# IN14_board.net
KiCad netlist of a schematic drawn in EAGLE
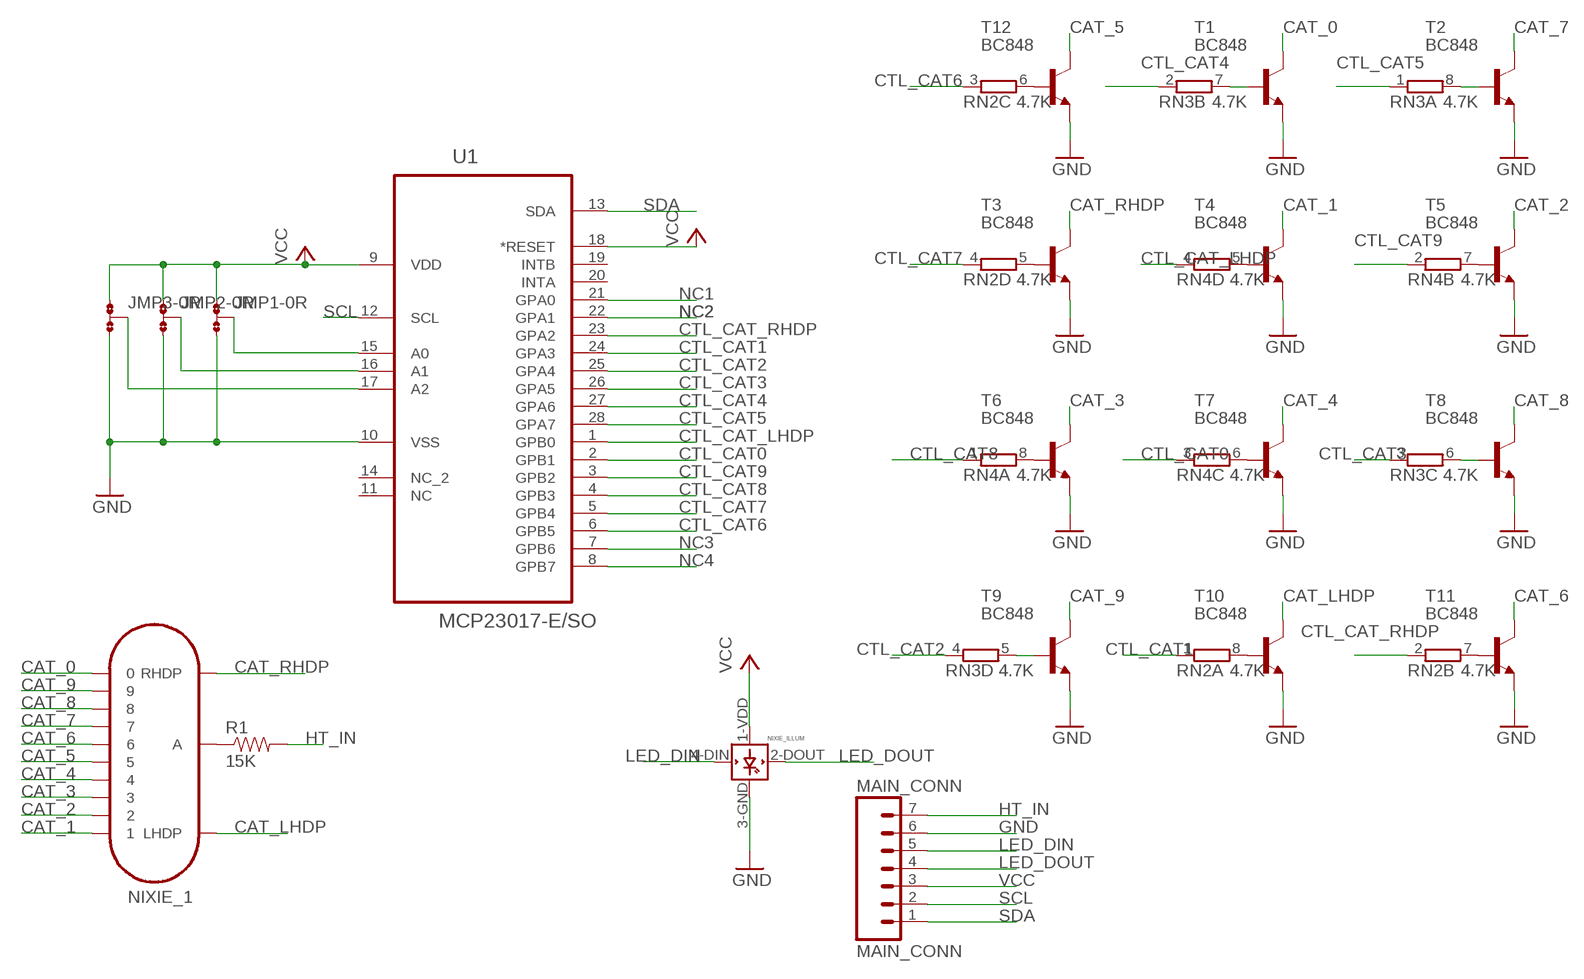
[diagram p0: schematic, sheet 1]

(export (version "E")
  (design (tool "Eeschema 10.0.6"))
  (components
    (comp (ref "JMP1")
      (value "0R-JUMPA")
      (footprint "eagle-import:A0R-JMP")
      (libsource (lib "eagle-import") (part "0R-JUMPA"))
    )
    (comp (ref "JMP2")
      (value "0R-JUMPA")
      (footprint "eagle-import:A0R-JMP")
      (libsource (lib "eagle-import") (part "0R-JUMPA"))
    )
    (comp (ref "JMP3")
      (value "0R-JUMPA")
      (footprint "eagle-import:A0R-JMP")
      (libsource (lib "eagle-import") (part "0R-JUMPA"))
    )
    (comp (ref "MAIN_CONN")
      (value "MAIN_CONN")
      (footprint "eagle-import:1X07_LONGPADS")
      (libsource (lib "eagle-import") (part "M07LONGPADS"))
    )
    (comp (ref "NIXIE_1")
      (value "IN-14")
      (footprint "eagle-import:IN-14")
      (libsource (lib "eagle-import") (part "IN-14"))
    )
    (comp (ref "NIXIE_ILLUM")
      (value "WS2812B")
      (footprint "eagle-import:WS2812B")
      (libsource (lib "eagle-import") (part "WS2812B"))
    )
    (comp (ref "R1")
      (value "15K")
      (footprint "eagle-import:0603-RES")
      (libsource (lib "eagle-import") (part "15KOHM1/10W1%(0603)0603"))
    )
    (comp (ref "RN2")
      (value "4.7K")
      (footprint "eagle-import:EXB38V")
      (libsource (lib "eagle-import") (part "4R-NEXB38V"))
    )
    (comp (ref "RN3")
      (value "4.7K")
      (footprint "eagle-import:EXB38V")
      (libsource (lib "eagle-import") (part "4R-NEXB38V"))
    )
    (comp (ref "RN4")
      (value "4.7K")
      (footprint "eagle-import:EXB38V")
      (libsource (lib "eagle-import") (part "4R-NEXB38V"))
    )
    (comp (ref "T1")
      (value "BC848")
      (footprint "eagle-import:SOT23")
      (libsource (lib "eagle-import") (part "BC848"))
    )
    (comp (ref "T2")
      (value "BC848")
      (footprint "eagle-import:SOT23")
      (libsource (lib "eagle-import") (part "BC848"))
    )
    (comp (ref "T3")
      (value "BC848")
      (footprint "eagle-import:SOT23")
      (libsource (lib "eagle-import") (part "BC848"))
    )
    (comp (ref "T4")
      (value "BC848")
      (footprint "eagle-import:SOT23")
      (libsource (lib "eagle-import") (part "BC848"))
    )
    (comp (ref "T5")
      (value "BC848")
      (footprint "eagle-import:SOT23")
      (libsource (lib "eagle-import") (part "BC848"))
    )
    (comp (ref "T6")
      (value "BC848")
      (footprint "eagle-import:SOT23")
      (libsource (lib "eagle-import") (part "BC848"))
    )
    (comp (ref "T7")
      (value "BC848")
      (footprint "eagle-import:SOT23")
      (libsource (lib "eagle-import") (part "BC848"))
    )
    (comp (ref "T8")
      (value "BC848")
      (footprint "eagle-import:SOT23")
      (libsource (lib "eagle-import") (part "BC848"))
    )
    (comp (ref "T9")
      (value "BC848")
      (footprint "eagle-import:SOT23")
      (libsource (lib "eagle-import") (part "BC848"))
    )
    (comp (ref "T10")
      (value "BC848")
      (footprint "eagle-import:SOT23")
      (libsource (lib "eagle-import") (part "BC848"))
    )
    (comp (ref "T11")
      (value "BC848")
      (footprint "eagle-import:SOT23")
      (libsource (lib "eagle-import") (part "BC848"))
    )
    (comp (ref "T12")
      (value "BC848")
      (footprint "eagle-import:SOT23")
      (libsource (lib "eagle-import") (part "BC848"))
    )
    (comp (ref "U1")
      (value "MCP23017-E/SO")
      (footprint "eagle-import:SOIC127P1032X265-28N")
      (libsource (lib "eagle-import") (part "MCP23017-E/SO"))
    )
  )
  (nets
    (net (code "1") (name "/CAT_0") (class "Default")
      (node (ref "NIXIE_1") (pin "0") (pinfunction "0_0") (pintype "bidirectional"))
      (node (ref "T1") (pin "3") (pinfunction "C_3") (pintype "passive"))
    )
    (net (code "2") (name "/CAT_1") (class "Default")
      (node (ref "NIXIE_1") (pin "1") (pinfunction "1_1") (pintype "bidirectional"))
      (node (ref "T4") (pin "3") (pinfunction "C_3") (pintype "passive"))
    )
    (net (code "3") (name "/CAT_2") (class "Default")
      (node (ref "NIXIE_1") (pin "2") (pinfunction "2_2") (pintype "bidirectional"))
      (node (ref "T5") (pin "3") (pinfunction "C_3") (pintype "passive"))
    )
    (net (code "4") (name "/CAT_3") (class "Default")
      (node (ref "NIXIE_1") (pin "3") (pinfunction "3_3") (pintype "bidirectional"))
      (node (ref "T6") (pin "3") (pinfunction "C_3") (pintype "passive"))
    )
    (net (code "5") (name "/CAT_4") (class "Default")
      (node (ref "NIXIE_1") (pin "4") (pinfunction "4_4") (pintype "bidirectional"))
      (node (ref "T7") (pin "3") (pinfunction "C_3") (pintype "passive"))
    )
    (net (code "6") (name "/CAT_5") (class "Default")
      (node (ref "NIXIE_1") (pin "5") (pinfunction "5_5") (pintype "bidirectional"))
      (node (ref "T12") (pin "3") (pinfunction "C_3") (pintype "passive"))
    )
    (net (code "7") (name "/CAT_6") (class "Default")
      (node (ref "NIXIE_1") (pin "6") (pinfunction "6_6") (pintype "bidirectional"))
      (node (ref "T11") (pin "3") (pinfunction "C_3") (pintype "passive"))
    )
    (net (code "8") (name "/CAT_7") (class "Default")
      (node (ref "NIXIE_1") (pin "7") (pinfunction "7_7") (pintype "bidirectional"))
      (node (ref "T2") (pin "3") (pinfunction "C_3") (pintype "passive"))
    )
    (net (code "9") (name "/CAT_8") (class "Default")
      (node (ref "NIXIE_1") (pin "8") (pinfunction "8_8") (pintype "bidirectional"))
      (node (ref "T8") (pin "3") (pinfunction "C_3") (pintype "passive"))
    )
    (net (code "10") (name "/CAT_9") (class "Default")
      (node (ref "NIXIE_1") (pin "9") (pinfunction "9_9") (pintype "bidirectional"))
      (node (ref "T9") (pin "3") (pinfunction "C_3") (pintype "passive"))
    )
    (net (code "11") (name "/CAT_LHDP") (class "Default")
      (node (ref "NIXIE_1") (pin "LHDP") (pinfunction "LHDP_LHDP") (pintype "bidirectional"))
      (node (ref "T10") (pin "3") (pinfunction "C_3") (pintype "passive"))
    )
    (net (code "12") (name "/CAT_RHDP") (class "Default")
      (node (ref "NIXIE_1") (pin "RHDP") (pinfunction "RHDP_RHDP") (pintype "bidirectional"))
      (node (ref "T3") (pin "3") (pinfunction "C_3") (pintype "passive"))
    )
    (net (code "13") (name "/CTL_CAT0") (class "Default")
      (node (ref "RN4") (pin "3") (pinfunction "1_3") (pintype "passive"))
      (node (ref "U1") (pin "2") (pinfunction "GPB1_2") (pintype "bidirectional"))
    )
    (net (code "14") (name "/CTL_CAT1") (class "Default")
      (node (ref "RN2") (pin "1") (pinfunction "1_1") (pintype "passive"))
      (node (ref "U1") (pin "24") (pinfunction "GPA3_24") (pintype "bidirectional"))
    )
    (net (code "15") (name "/CTL_CAT2") (class "Default")
      (node (ref "RN3") (pin "4") (pinfunction "1_4") (pintype "passive"))
      (node (ref "U1") (pin "25") (pinfunction "GPA4_25") (pintype "bidirectional"))
    )
    (net (code "16") (name "/CTL_CAT3") (class "Default")
      (node (ref "RN3") (pin "3") (pinfunction "1_3") (pintype "passive"))
      (node (ref "U1") (pin "26") (pinfunction "GPA5_26") (pintype "bidirectional"))
    )
    (net (code "17") (name "/CTL_CAT4") (class "Default")
      (node (ref "RN3") (pin "2") (pinfunction "1_2") (pintype "passive"))
      (node (ref "U1") (pin "27") (pinfunction "GPA6_27") (pintype "bidirectional"))
    )
    (net (code "18") (name "/CTL_CAT5") (class "Default")
      (node (ref "RN3") (pin "1") (pinfunction "1_1") (pintype "passive"))
      (node (ref "U1") (pin "28") (pinfunction "GPA7_28") (pintype "bidirectional"))
    )
    (net (code "19") (name "/CTL_CAT6") (class "Default")
      (node (ref "RN2") (pin "3") (pinfunction "1_3") (pintype "passive"))
      (node (ref "U1") (pin "6") (pinfunction "GPB5_6") (pintype "bidirectional"))
    )
    (net (code "20") (name "/CTL_CAT7") (class "Default")
      (node (ref "RN2") (pin "4") (pinfunction "1_4") (pintype "passive"))
      (node (ref "U1") (pin "5") (pinfunction "GPB4_5") (pintype "bidirectional"))
    )
    (net (code "21") (name "/CTL_CAT8") (class "Default")
      (node (ref "RN4") (pin "1") (pinfunction "1_1") (pintype "passive"))
      (node (ref "U1") (pin "4") (pinfunction "GPB3_4") (pintype "bidirectional"))
    )
    (net (code "22") (name "/CTL_CAT9") (class "Default")
      (node (ref "RN4") (pin "2") (pinfunction "1_2") (pintype "passive"))
      (node (ref "U1") (pin "3") (pinfunction "GPB2_3") (pintype "bidirectional"))
    )
    (net (code "23") (name "/CTL_CAT_LHDP") (class "Default")
      (node (ref "RN4") (pin "4") (pinfunction "1_4") (pintype "passive"))
      (node (ref "U1") (pin "1") (pinfunction "GPB0_1") (pintype "bidirectional"))
    )
    (net (code "24") (name "/CTL_CAT_RHDP") (class "Default")
      (node (ref "RN2") (pin "2") (pinfunction "1_2") (pintype "passive"))
      (node (ref "U1") (pin "23") (pinfunction "GPA2_23") (pintype "bidirectional"))
    )
    (net (code "25") (name "/HT_IN") (class "Default")
      (node (ref "MAIN_CONN") (pin "7") (pinfunction "7_7") (pintype "passive"))
      (node (ref "R1") (pin "2") (pinfunction "2_2") (pintype "passive"))
    )
    (net (code "26") (name "/LED_DIN") (class "Default")
      (node (ref "MAIN_CONN") (pin "5") (pinfunction "5_5") (pintype "passive"))
      (node (ref "NIXIE_ILLUM") (pin "4-DIN") (pinfunction "DIN_4-DIN") (pintype "input"))
    )
    (net (code "27") (name "/LED_DOUT") (class "Default")
      (node (ref "MAIN_CONN") (pin "4") (pinfunction "4_4") (pintype "passive"))
      (node (ref "NIXIE_ILLUM") (pin "2-DOUT") (pinfunction "DOUT_2-DOUT") (pintype "output"))
    )
    (net (code "28") (name "/NC1") (class "Default")
      (node (ref "U1") (pin "21") (pinfunction "GPA0_21") (pintype "bidirectional"))
    )
    (net (code "29") (name "/NC2") (class "Default")
      (node (ref "U1") (pin "22") (pinfunction "GPA1_22") (pintype "bidirectional"))
    )
    (net (code "30") (name "/NC3") (class "Default")
      (node (ref "U1") (pin "7") (pinfunction "GPB6_7") (pintype "bidirectional"))
    )
    (net (code "31") (name "/NC4") (class "Default")
      (node (ref "U1") (pin "8") (pinfunction "GPB7_8") (pintype "bidirectional"))
    )
    (net (code "32") (name "/SCL") (class "Default")
      (node (ref "MAIN_CONN") (pin "2") (pinfunction "2_2") (pintype "passive"))
      (node (ref "U1") (pin "12") (pinfunction "SCL_12") (pintype "input"))
    )
    (net (code "33") (name "/SDA") (class "Default")
      (node (ref "MAIN_CONN") (pin "1") (pinfunction "1_1") (pintype "passive"))
      (node (ref "U1") (pin "13") (pinfunction "SDA_13") (pintype "bidirectional"))
    )
    (net (code "34") (name "GND") (class "Default")
      (node (ref "JMP1") (pin "3") (pinfunction "3_3") (pintype "passive"))
      (node (ref "JMP2") (pin "3") (pinfunction "3_3") (pintype "passive"))
      (node (ref "JMP3") (pin "3") (pinfunction "3_3") (pintype "passive"))
      (node (ref "MAIN_CONN") (pin "6") (pinfunction "6_6") (pintype "passive"))
      (node (ref "NIXIE_ILLUM") (pin "3-GND") (pinfunction "GND_3-GND") (pintype "bidirectional"))
      (node (ref "T1") (pin "2") (pinfunction "E_2") (pintype "passive"))
      (node (ref "T10") (pin "2") (pinfunction "E_2") (pintype "passive"))
      (node (ref "T11") (pin "2") (pinfunction "E_2") (pintype "passive"))
      (node (ref "T12") (pin "2") (pinfunction "E_2") (pintype "passive"))
      (node (ref "T2") (pin "2") (pinfunction "E_2") (pintype "passive"))
      (node (ref "T3") (pin "2") (pinfunction "E_2") (pintype "passive"))
      (node (ref "T4") (pin "2") (pinfunction "E_2") (pintype "passive"))
      (node (ref "T5") (pin "2") (pinfunction "E_2") (pintype "passive"))
      (node (ref "T6") (pin "2") (pinfunction "E_2") (pintype "passive"))
      (node (ref "T7") (pin "2") (pinfunction "E_2") (pintype "passive"))
      (node (ref "T8") (pin "2") (pinfunction "E_2") (pintype "passive"))
      (node (ref "T9") (pin "2") (pinfunction "E_2") (pintype "passive"))
      (node (ref "U1") (pin "10") (pinfunction "VSS_10") (pintype "power_in"))
    )
    (net (code "35") (name "Net-(NIXIE_1-PadA)") (class "Default")
      (node (ref "NIXIE_1") (pin "A") (pinfunction "A_A") (pintype "bidirectional"))
      (node (ref "R1") (pin "1") (pinfunction "1_1") (pintype "passive"))
    )
    (net (code "36") (name "Net-(RN2A-2)") (class "Default")
      (node (ref "RN2") (pin "8") (pinfunction "2_8") (pintype "passive"))
      (node (ref "T10") (pin "1") (pinfunction "B_1") (pintype "passive"))
    )
    (net (code "37") (name "Net-(RN2B-2)") (class "Default")
      (node (ref "RN2") (pin "7") (pinfunction "2_7") (pintype "passive"))
      (node (ref "T11") (pin "1") (pinfunction "B_1") (pintype "passive"))
    )
    (net (code "38") (name "Net-(RN2C-2)") (class "Default")
      (node (ref "RN2") (pin "6") (pinfunction "2_6") (pintype "passive"))
      (node (ref "T12") (pin "1") (pinfunction "B_1") (pintype "passive"))
    )
    (net (code "39") (name "Net-(RN2D-2)") (class "Default")
      (node (ref "RN2") (pin "5") (pinfunction "2_5") (pintype "passive"))
      (node (ref "T3") (pin "1") (pinfunction "B_1") (pintype "passive"))
    )
    (net (code "40") (name "Net-(RN3A-2)") (class "Default")
      (node (ref "RN3") (pin "8") (pinfunction "2_8") (pintype "passive"))
      (node (ref "T2") (pin "1") (pinfunction "B_1") (pintype "passive"))
    )
    (net (code "41") (name "Net-(RN3B-2)") (class "Default")
      (node (ref "RN3") (pin "7") (pinfunction "2_7") (pintype "passive"))
      (node (ref "T1") (pin "1") (pinfunction "B_1") (pintype "passive"))
    )
    (net (code "42") (name "Net-(RN3C-2)") (class "Default")
      (node (ref "RN3") (pin "6") (pinfunction "2_6") (pintype "passive"))
      (node (ref "T8") (pin "1") (pinfunction "B_1") (pintype "passive"))
    )
    (net (code "43") (name "Net-(RN3D-2)") (class "Default")
      (node (ref "RN3") (pin "5") (pinfunction "2_5") (pintype "passive"))
      (node (ref "T9") (pin "1") (pinfunction "B_1") (pintype "passive"))
    )
    (net (code "44") (name "Net-(RN4A-2)") (class "Default")
      (node (ref "RN4") (pin "8") (pinfunction "2_8") (pintype "passive"))
      (node (ref "T6") (pin "1") (pinfunction "B_1") (pintype "passive"))
    )
    (net (code "45") (name "Net-(RN4B-2)") (class "Default")
      (node (ref "RN4") (pin "7") (pinfunction "2_7") (pintype "passive"))
      (node (ref "T5") (pin "1") (pinfunction "B_1") (pintype "passive"))
    )
    (net (code "46") (name "Net-(RN4C-2)") (class "Default")
      (node (ref "RN4") (pin "6") (pinfunction "2_6") (pintype "passive"))
      (node (ref "T7") (pin "1") (pinfunction "B_1") (pintype "passive"))
    )
    (net (code "47") (name "Net-(RN4D-2)") (class "Default")
      (node (ref "RN4") (pin "5") (pinfunction "2_5") (pintype "passive"))
      (node (ref "T4") (pin "1") (pinfunction "B_1") (pintype "passive"))
    )
    (net (code "48") (name "Net-(U1-A0)") (class "Default")
      (node (ref "JMP1") (pin "2") (pinfunction "2_2") (pintype "passive"))
      (node (ref "U1") (pin "15") (pinfunction "A0_15") (pintype "input"))
    )
    (net (code "49") (name "Net-(U1-A1)") (class "Default")
      (node (ref "JMP2") (pin "2") (pinfunction "2_2") (pintype "passive"))
      (node (ref "U1") (pin "16") (pinfunction "A1_16") (pintype "input"))
    )
    (net (code "50") (name "Net-(U1-A2)") (class "Default")
      (node (ref "JMP3") (pin "2") (pinfunction "2_2") (pintype "passive"))
      (node (ref "U1") (pin "17") (pinfunction "A2_17") (pintype "input"))
    )
    (net (code "51") (name "VCC") (class "Default")
      (node (ref "JMP1") (pin "1") (pinfunction "1_1") (pintype "passive"))
      (node (ref "JMP2") (pin "1") (pinfunction "1_1") (pintype "passive"))
      (node (ref "JMP3") (pin "1") (pinfunction "1_1") (pintype "passive"))
      (node (ref "MAIN_CONN") (pin "3") (pinfunction "3_3") (pintype "passive"))
      (node (ref "NIXIE_ILLUM") (pin "1-VDD") (pinfunction "VDD_1-VDD") (pintype "bidirectional"))
      (node (ref "U1") (pin "18") (pinfunction "*RESET_18") (pintype "output"))
      (node (ref "U1") (pin "9") (pinfunction "VDD_9") (pintype "power_in"))
    )
    (net (code "52") (name "unconnected-(U1-INTA-Pad20)") (class "Default")
      (node (ref "U1") (pin "20") (pinfunction "INTA_20") (pintype "output"))
    )
    (net (code "53") (name "unconnected-(U1-INTB-Pad19)") (class "Default")
      (node (ref "U1") (pin "19") (pinfunction "INTB_19") (pintype "output"))
    )
    (net (code "54") (name "unconnected-(U1-NC-Pad11)") (class "Default")
      (node (ref "U1") (pin "11") (pinfunction "NC_11") (pintype "no_connect"))
    )
    (net (code "55") (name "unconnected-(U1-NC_2-Pad14)") (class "Default")
      (node (ref "U1") (pin "14") (pinfunction "NC_2_14") (pintype "no_connect"))
    )
  )
)
